# Main_Schematics.net
KiCad netlist of a schematic drawn in Altium Designer
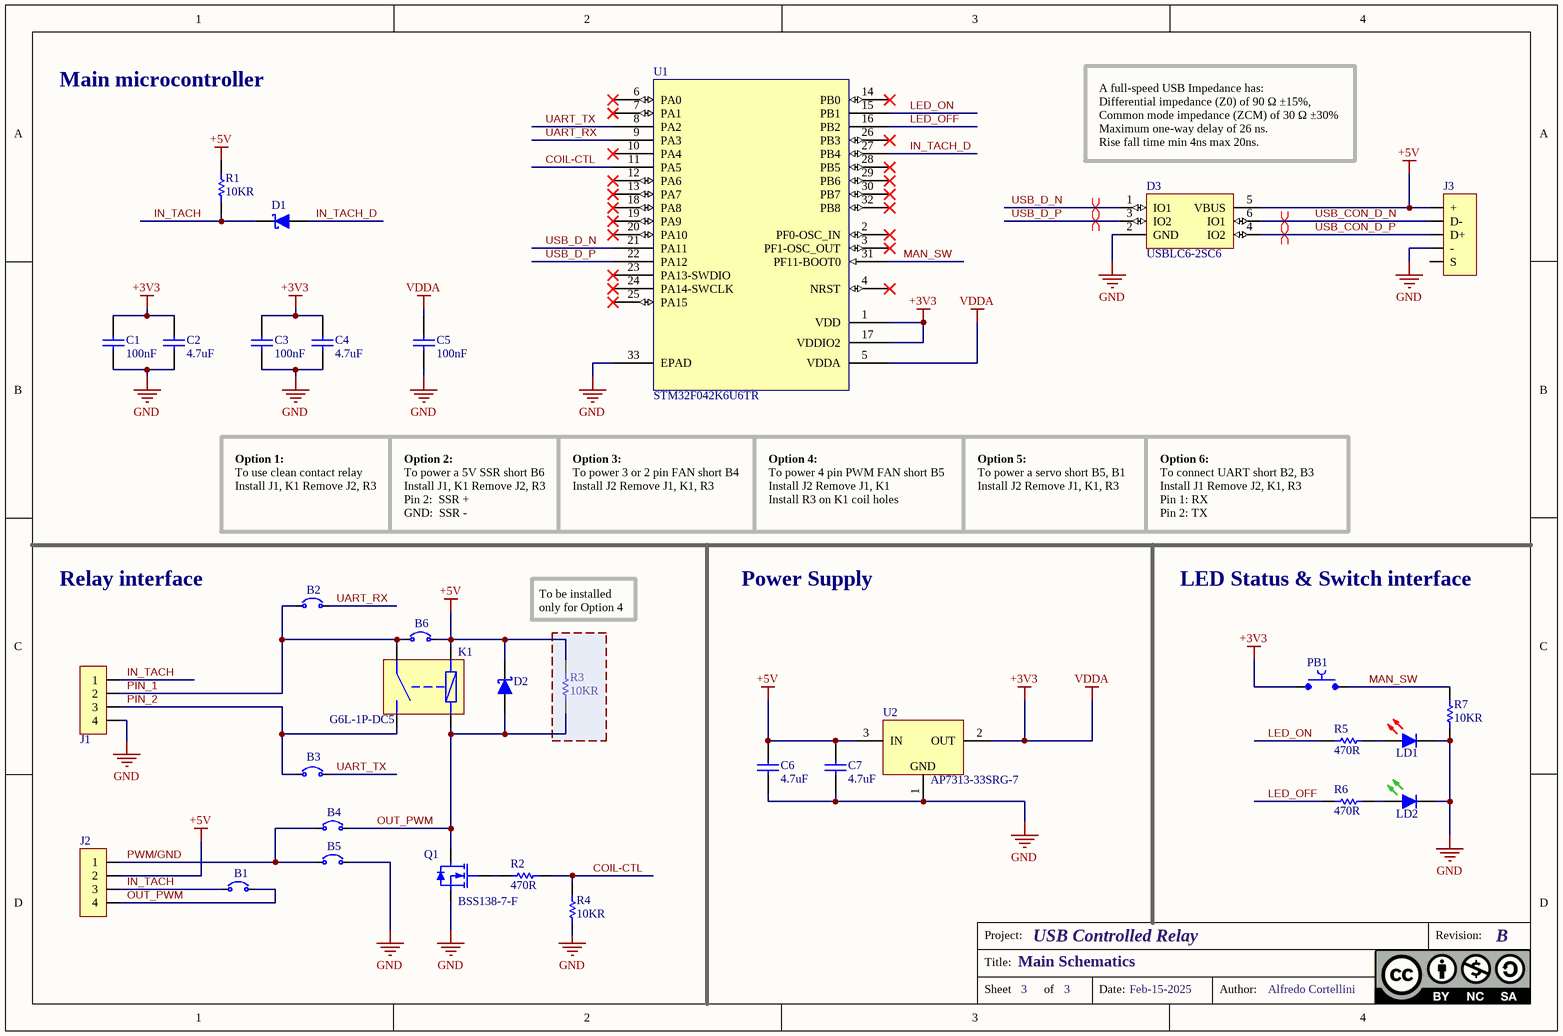
[diagram p0: Main Schematics.SchDoc]

(export (version "E")
  (design (tool "Eeschema 10.0.6"))
  (components
    (comp (ref "B1")
      (value "_SMD-JUMP-0603")
      (footprint "_SMD-JUMP-0603")
      (description "Option Jumper smd 0603")
      (libsource (lib "IT Logic Library") (part "_SMD-JUMP-0603"))
    )
    (comp (ref "B2")
      (value "_SMD-JUMP-0603")
      (footprint "_SMD-JUMP-0603")
      (description "Option Jumper smd 0603")
      (libsource (lib "IT Logic Library") (part "_SMD-JUMP-0603"))
    )
    (comp (ref "B3")
      (value "_SMD-JUMP-0603")
      (footprint "_SMD-JUMP-0603")
      (description "Option Jumper smd 0603")
      (libsource (lib "IT Logic Library") (part "_SMD-JUMP-0603"))
    )
    (comp (ref "B4")
      (value "_SMD-JUMP-0603")
      (footprint "_SMD-JUMP-0603")
      (description "Option Jumper smd 0603")
      (libsource (lib "IT Logic Library") (part "_SMD-JUMP-0603"))
    )
    (comp (ref "B5")
      (value "_SMD-JUMP-0603")
      (footprint "_SMD-JUMP-0603")
      (description "Option Jumper smd 0603")
      (libsource (lib "IT Logic Library") (part "_SMD-JUMP-0603"))
    )
    (comp (ref "B6")
      (value "_SMD-JUMP-0603")
      (footprint "_SMD-JUMP-0603")
      (description "Option Jumper smd 0603")
      (libsource (lib "IT Logic Library") (part "_SMD-JUMP-0603"))
    )
    (comp (ref "C1")
      (value "100nF")
      (footprint "C0603-H90")
      (description "Cap 0603 Case Ceramic 100nF 50V X7R")
      (fields
        (field (name "MANUFACTURER") "TDK")
        (field (name "MANUFACTURER PART NUMBER") "CGA3E2X7R1H104K080AA")
      )
      (libsource (lib "IT Logic Library") (part "CGA3E2X7R1H104K080AA"))
    )
    (comp (ref "C2")
      (value "4.7uF")
      (footprint "C0603-H90")
      (description "Cap 0603 Case Ceramic 4.7uF 16V X7R")
      (fields
        (field (name "MANUFACTURER") "Murata")
        (field (name "MANUFACTURER PART NUMBER") "GRM188Z71C475KE21D")
      )
      (libsource (lib "IT Logic Library") (part "GRM188Z71C475KE21D"))
    )
    (comp (ref "C3")
      (value "100nF")
      (footprint "C0603-H90")
      (description "Cap 0603 Case Ceramic 100nF 50V X7R")
      (fields
        (field (name "MANUFACTURER") "TDK")
        (field (name "MANUFACTURER PART NUMBER") "CGA3E2X7R1H104K080AA")
      )
      (libsource (lib "IT Logic Library") (part "CGA3E2X7R1H104K080AA"))
    )
    (comp (ref "C4")
      (value "4.7uF")
      (footprint "C0603-H90")
      (description "Cap 0603 Case Ceramic 4.7uF 16V X7R")
      (fields
        (field (name "MANUFACTURER") "Murata")
        (field (name "MANUFACTURER PART NUMBER") "GRM188Z71C475KE21D")
      )
      (libsource (lib "IT Logic Library") (part "GRM188Z71C475KE21D"))
    )
    (comp (ref "C5")
      (value "100nF")
      (footprint "C0603-H90")
      (description "Cap 0603 Case Ceramic 100nF 50V X7R")
      (fields
        (field (name "MANUFACTURER") "TDK")
        (field (name "MANUFACTURER PART NUMBER") "CGA3E2X7R1H104K080AA")
      )
      (libsource (lib "IT Logic Library") (part "CGA3E2X7R1H104K080AA"))
    )
    (comp (ref "C6")
      (value "4.7uF")
      (footprint "C0603-H90")
      (description "Cap 0603 Case Ceramic 4.7uF 16V X7R")
      (fields
        (field (name "MANUFACTURER") "Murata")
        (field (name "MANUFACTURER PART NUMBER") "GRM188Z71C475KE21D")
      )
      (libsource (lib "IT Logic Library") (part "GRM188Z71C475KE21D"))
    )
    (comp (ref "C7")
      (value "4.7uF")
      (footprint "C0603-H90")
      (description "Cap 0603 Case Ceramic 4.7uF 16V X7R")
      (fields
        (field (name "MANUFACTURER") "Murata")
        (field (name "MANUFACTURER PART NUMBER") "GRM188Z71C475KE21D")
      )
      (libsource (lib "IT Logic Library") (part "GRM188Z71C475KE21D"))
    )
    (comp (ref "D1")
      (value "BAT54WS-7-F")
      (footprint "SOD-323")
      (description "Diode Schottky 30V 0.1A, Vf 400mV@10mA SOD-323")
      (fields (field (name "MANUFACTURER") "Diodes"))
      (libsource (lib "IT Logic Library") (part "BAT54WS-7-F"))
    )
    (comp (ref "D2")
      (value "BAT54WS-7-F")
      (footprint "SOD-323")
      (description "Diode Schottky 30V 0.1A, Vf 400mV@10mA SOD-323")
      (fields (field (name "MANUFACTURER") "Diodes"))
      (libsource (lib "IT Logic Library") (part "BAT54WS-7-F"))
    )
    (comp (ref "D3")
      (value "USBLC6-2SC6")
      (footprint "SOT-236")
      (description "ESD Protection Diodes / TVS Diodes 2 Line 2.5pF USB 2.0 ESD Protect SOT23-6")
      (fields (field (name "MANUFACTURER") "STMicroelectronics"))
      (libsource (lib "IT Logic Library") (part "USBLC6-2SC6"))
    )
    (comp (ref "J1")
      (value "691210910004")
      (footprint "691210910004")
      (description "Conn Term Block Header Screw 2.54 mm 4 Pos 6A 150V")
      (fields (field (name "MANUFACTURER") "Wurth Electronics"))
      (libsource (lib "IT Logic Library") (part "691210910004"))
    )
    (comp (ref "J2")
      (value "CO975")
      (footprint "FAN-HDR-4P-90DEG")
      (description "Conn Post Header - PWM Fan - 90 Deg - 4 Pos - Series KK254")
      (fields (field (name "MANUFACTURER") "Moddy"))
      (libsource (lib "IT Logic Library") (part "CO975"))
    )
    (comp (ref "J3")
      (value "USB-AP-S-RA")
      (footprint "48037-0001")
      (description "Conn USB Type A Plug Right-Anglel TH")
      (fields (field (name "MANUFACTURER") "Adam Tech"))
      (libsource (lib "IT Logic Library") (part "USB-AP-S-RA"))
    )
    (comp (ref "K1")
      (value "G6L-1P-DC5")
      (footprint "G6L-1P")
      (description "Relay Low Signal Sealed SPST-NO 1A 5VDC Through Hole Tube")
      (fields (field (name "MANUFACTURER") "Omron"))
      (libsource (lib "IT Logic Library") (part "G6L-1P-DC5"))
    )
    (comp (ref "LD1")
      (value "LTST-C191KRKT")
      (footprint "LED-0603-R")
      (description "LED 0603 Top Red 631nm 2-Pin")
      (fields (field (name "MANUFACTURER") "Vishay Semiconductors"))
      (libsource (lib "IT Logic Library") (part "LTST-C191KRKT"))
    )
    (comp (ref "LD2")
      (value "LTST-C191KGKT")
      (footprint "LED-0603-G")
      (description "LED 0603 Top Green 571nm 2-Pin")
      (fields (field (name "MANUFACTURER") "Vishay Semiconductors"))
      (libsource (lib "IT Logic Library") (part "LTST-C191KGKT"))
    )
    (comp (ref "PB1")
      (value "SKQMAQE010")
      (footprint "SKQMA-SERIE")
      (description "Tactile Switch Rectangular 6.00x3.55mm. Height 4.3mm. J-Lead 50mA 12VDC 260gf SMD")
      (fields (field (name "MANUFACTURER") "Alps Alpine"))
      (libsource (lib "IT Logic Library") (part "SKQMAQE010"))
    )
    (comp (ref "Q1")
      (value "BSS138-7-F")
      (footprint "SOT-23")
      (description "Mosfet N 50V Vds 20V Vgs 1.4R SOT-23")
      (fields (field (name "MANUFACTURER") "Diodes"))
      (libsource (lib "IT Logic Library") (part "BSS138-7-F"))
    )
    (comp (ref "R1")
      (value "10KR")
      (footprint "R0603-H55")
      (description "Resistor 0603 Case 10KR 1% 1/10W")
      (fields
        (field (name "MANUFACTURER") "Yageo")
        (field (name "MANUFACTURER PART NUMBER") "RC0603FR-0710KL")
      )
      (libsource (lib "IT Logic Library") (part "RC0603FR-0710KL"))
    )
    (comp (ref "R2")
      (value "470R")
      (footprint "R0603-H55")
      (description "Resistor 0603 Case 470R 1% 1/10W")
      (fields
        (field (name "MANUFACTURER") "Yageo")
        (field (name "MANUFACTURER PART NUMBER") "RC0603FR-07470RL")
      )
      (libsource (lib "IT Logic Library") (part "RC0603FR-07470RL"))
    )
    (comp (ref "R3")
      (value "10KR")
      (footprint "RAXIAL-1/8W")
      (description "Resistor Axial 10KR 1% 1/8W")
      (fields
        (field (name "MANUFACTURER") "SEI Stackpole")
        (field (name "MANUFACTURER PART NUMBER") "RNF18FTD10K0")
      )
      (libsource (lib "IT Logic Library") (part "RNF18FTD10K0"))
    )
    (comp (ref "R4")
      (value "10KR")
      (footprint "R0603-H55")
      (description "Resistor 0603 Case 10KR 1% 1/10W")
      (fields
        (field (name "MANUFACTURER") "Yageo")
        (field (name "MANUFACTURER PART NUMBER") "RC0603FR-0710KL")
      )
      (libsource (lib "IT Logic Library") (part "RC0603FR-0710KL"))
    )
    (comp (ref "R5")
      (value "470R")
      (footprint "R0603-H55")
      (description "Resistor 0603 Case 470R 1% 1/10W")
      (fields
        (field (name "MANUFACTURER") "Yageo")
        (field (name "MANUFACTURER PART NUMBER") "RC0603FR-07470RL")
      )
      (libsource (lib "IT Logic Library") (part "RC0603FR-07470RL"))
    )
    (comp (ref "R6")
      (value "470R")
      (footprint "R0603-H55")
      (description "Resistor 0603 Case 470R 1% 1/10W")
      (fields
        (field (name "MANUFACTURER") "Yageo")
        (field (name "MANUFACTURER PART NUMBER") "RC0603FR-07470RL")
      )
      (libsource (lib "IT Logic Library") (part "RC0603FR-07470RL"))
    )
    (comp (ref "R7")
      (value "10KR")
      (footprint "R0603-H55")
      (description "Resistor 0603 Case 10KR 1% 1/10W")
      (fields
        (field (name "MANUFACTURER") "Yageo")
        (field (name "MANUFACTURER PART NUMBER") "RC0603FR-0710KL")
      )
      (libsource (lib "IT Logic Library") (part "RC0603FR-0710KL"))
    )
    (comp (ref "U1")
      (value "STM32F042K6U6TR")
      (footprint "UFQFPN32-5x5")
      (description "STM32 Arm Cortex-M0 USB line MCU 32 Kbytes of Flash 48 MHz CPU USB CAN CEC")
      (fields (field (name "MANUFACTURER") "STMicroelectronics"))
      (libsource (lib "IT Logic Library") (part "STM32F042K6U6TR"))
    )
    (comp (ref "U2")
      (value "AP7313-33SRG-7")
      (footprint "SOT-23")
      (description "LDO 3.3V 150mA Out  6Vin 130mV Dropout, Quiescent current 65uA Startup 80µs SOT-23")
      (fields (field (name "MANUFACTURER") "Diodes"))
      (libsource (lib "IT Logic Library") (part "AP7313-33SRG-7"))
    )
  )
  (nets
    (net (code "1") (name "+3V3") (class "Default")
      (node (ref "C1") (pin "2") (pinfunction "2_2") (pintype "passive"))
      (node (ref "C2") (pin "2") (pinfunction "2_2") (pintype "passive"))
      (node (ref "C3") (pin "2") (pinfunction "2_2") (pintype "passive"))
      (node (ref "C4") (pin "2") (pinfunction "2_2") (pintype "passive"))
      (node (ref "C5") (pin "2") (pinfunction "2_2") (pintype "passive"))
      (node (ref "PB1") (pin "1") (pinfunction "1_1") (pintype "passive"))
      (node (ref "U1") (pin "1") (pinfunction "VDD_1") (pintype "power_in"))
      (node (ref "U1") (pin "17") (pinfunction "VDDIO2_17") (pintype "power_in"))
      (node (ref "U1") (pin "5") (pinfunction "VDDA_5") (pintype "power_in"))
      (node (ref "U2") (pin "2") (pinfunction "OUT_2") (pintype "power_in"))
    )
    (net (code "2") (name "+5V") (class "Default")
      (node (ref "B6") (pin "1") (pinfunction "1_1") (pintype "passive"))
      (node (ref "C6") (pin "2") (pinfunction "2_2") (pintype "passive"))
      (node (ref "C7") (pin "2") (pinfunction "2_2") (pintype "passive"))
      (node (ref "D2") (pin "1") (pinfunction "K_1") (pintype "passive"))
      (node (ref "D3") (pin "5") (pinfunction "VBUS_5") (pintype "power_in"))
      (node (ref "J2") (pin "2") (pinfunction "2_2") (pintype "passive"))
      (node (ref "J3") (pin "1") (pinfunction "+_1") (pintype "passive"))
      (node (ref "K1") (pin "8") (pintype "passive"))
      (node (ref "R1") (pin "2") (pinfunction "2_2") (pintype "passive"))
      (node (ref "R3") (pin "2") (pinfunction "2_2") (pintype "passive"))
      (node (ref "U2") (pin "3") (pinfunction "IN_3") (pintype "power_in"))
    )
    (net (code "3") (name "/COIL-CTL") (class "Default")
      (node (ref "R2") (pin "2") (pinfunction "2_2") (pintype "passive"))
      (node (ref "R4") (pin "2") (pinfunction "2_2") (pintype "passive"))
      (node (ref "U1") (pin "11") (pinfunction "PA5_11") (pintype "passive"))
    )
    (net (code "4") (name "/IN_TACH") (class "Default")
      (node (ref "B1") (pin "2") (pinfunction "2_2") (pintype "passive"))
      (node (ref "D1") (pin "1") (pinfunction "K_1") (pintype "passive"))
      (node (ref "J1") (pin "1") (pinfunction "1_1") (pintype "passive"))
      (node (ref "J2") (pin "3") (pinfunction "3_3") (pintype "passive"))
      (node (ref "R1") (pin "1") (pinfunction "1_1") (pintype "passive"))
    )
    (net (code "5") (name "/IN_TACH_D") (class "Default")
      (node (ref "D1") (pin "2") (pinfunction "A_2") (pintype "passive"))
      (node (ref "U1") (pin "27") (pinfunction "PB4_27") (pintype "bidirectional"))
    )
    (net (code "6") (name "/LED_OFF") (class "Default")
      (node (ref "R6") (pin "1") (pinfunction "1_1") (pintype "passive"))
      (node (ref "U1") (pin "16") (pinfunction "PB2_16") (pintype "passive"))
    )
    (net (code "7") (name "/LED_ON") (class "Default")
      (node (ref "R5") (pin "1") (pinfunction "1_1") (pintype "passive"))
      (node (ref "U1") (pin "15") (pinfunction "PB1_15") (pintype "passive"))
    )
    (net (code "8") (name "/MAN_SW") (class "Default")
      (node (ref "PB1") (pin "2") (pinfunction "2_2") (pintype "passive"))
      (node (ref "R7") (pin "2") (pinfunction "2_2") (pintype "passive"))
      (node (ref "U1") (pin "31") (pinfunction "PF11-BOOT0_31") (pintype "input"))
    )
    (net (code "9") (name "/OUT_PWM") (class "Default")
      (node (ref "B1") (pin "1") (pinfunction "1_1") (pintype "passive"))
      (node (ref "B4") (pin "1") (pinfunction "1_1") (pintype "passive"))
      (node (ref "D2") (pin "2") (pinfunction "A_2") (pintype "passive"))
      (node (ref "J2") (pin "4") (pinfunction "4_4") (pintype "passive"))
      (node (ref "K1") (pin "5") (pintype "passive"))
      (node (ref "Q1") (pin "3") (pinfunction "D_3") (pintype "passive"))
      (node (ref "R3") (pin "1") (pinfunction "1_1") (pintype "passive"))
    )
    (net (code "10") (name "/PIN_1") (class "Default")
      (node (ref "B2") (pin "2") (pinfunction "2_2") (pintype "passive"))
      (node (ref "B6") (pin "2") (pinfunction "2_2") (pintype "passive"))
      (node (ref "J1") (pin "2") (pinfunction "2_2") (pintype "passive"))
      (node (ref "K1") (pin "2") (pinfunction "C_2") (pintype "passive"))
    )
    (net (code "11") (name "/PIN_2") (class "Default")
      (node (ref "B3") (pin "2") (pinfunction "2_2") (pintype "passive"))
      (node (ref "J1") (pin "3") (pinfunction "3_3") (pintype "passive"))
      (node (ref "K1") (pin "4") (pinfunction "NO_4") (pintype "passive"))
    )
    (net (code "12") (name "/PWM{slash}GND") (class "Default")
      (node (ref "B4") (pin "2") (pinfunction "2_2") (pintype "passive"))
      (node (ref "B5") (pin "2") (pinfunction "2_2") (pintype "passive"))
      (node (ref "J2") (pin "1") (pinfunction "1_1") (pintype "passive"))
    )
    (net (code "13") (name "/UART_RX") (class "Default")
      (node (ref "B2") (pin "1") (pinfunction "1_1") (pintype "passive"))
      (node (ref "U1") (pin "9") (pinfunction "PA3_9") (pintype "passive"))
    )
    (net (code "14") (name "/UART_TX") (class "Default")
      (node (ref "B3") (pin "1") (pinfunction "1_1") (pintype "passive"))
      (node (ref "U1") (pin "8") (pinfunction "PA2_8") (pintype "passive"))
    )
    (net (code "15") (name "/USB_CON_D_N") (class "Default")
      (node (ref "D3") (pin "6") (pinfunction "IO1_6") (pintype "bidirectional"))
      (node (ref "J3") (pin "2") (pinfunction "D-_2") (pintype "passive"))
    )
    (net (code "16") (name "/USB_CON_D_P") (class "Default")
      (node (ref "D3") (pin "4") (pinfunction "IO2_4") (pintype "bidirectional"))
      (node (ref "J3") (pin "3") (pinfunction "D+_3") (pintype "passive"))
    )
    (net (code "17") (name "/USB_D_N") (class "Default")
      (node (ref "D3") (pin "1") (pinfunction "IO1_1") (pintype "bidirectional"))
      (node (ref "U1") (pin "21") (pinfunction "PA11_21") (pintype "passive"))
    )
    (net (code "18") (name "/USB_D_P") (class "Default")
      (node (ref "D3") (pin "3") (pinfunction "IO2_3") (pintype "bidirectional"))
      (node (ref "U1") (pin "22") (pinfunction "PA12_22") (pintype "passive"))
    )
    (net (code "19") (name "GND") (class "Default")
      (node (ref "B5") (pin "1") (pinfunction "1_1") (pintype "passive"))
      (node (ref "C1") (pin "1") (pinfunction "1_1") (pintype "passive"))
      (node (ref "C2") (pin "1") (pinfunction "1_1") (pintype "passive"))
      (node (ref "C3") (pin "1") (pinfunction "1_1") (pintype "passive"))
      (node (ref "C4") (pin "1") (pinfunction "1_1") (pintype "passive"))
      (node (ref "C5") (pin "1") (pinfunction "1_1") (pintype "passive"))
      (node (ref "C6") (pin "1") (pinfunction "1_1") (pintype "passive"))
      (node (ref "C7") (pin "1") (pinfunction "1_1") (pintype "passive"))
      (node (ref "D3") (pin "2") (pinfunction "GND_2") (pintype "power_in"))
      (node (ref "J1") (pin "4") (pinfunction "4_4") (pintype "passive"))
      (node (ref "J3") (pin "4") (pinfunction "-_4") (pintype "passive"))
      (node (ref "LD1") (pin "1") (pinfunction "K_1") (pintype "passive"))
      (node (ref "LD2") (pin "1") (pinfunction "K_1") (pintype "passive"))
      (node (ref "Q1") (pin "2") (pinfunction "S_2") (pintype "passive"))
      (node (ref "R4") (pin "1") (pinfunction "1_1") (pintype "passive"))
      (node (ref "R7") (pin "1") (pinfunction "1_1") (pintype "passive"))
      (node (ref "U1") (pin "33") (pinfunction "EPAD_33") (pintype "passive"))
      (node (ref "U2") (pin "1") (pinfunction "GND_1") (pintype "power_in"))
    )
    (net (code "20") (name "Net-(LD1-A)") (class "Default")
      (node (ref "LD1") (pin "2") (pinfunction "A_2") (pintype "passive"))
      (node (ref "R5") (pin "2") (pinfunction "2_2") (pintype "passive"))
    )
    (net (code "21") (name "Net-(LD2-A)") (class "Default")
      (node (ref "LD2") (pin "2") (pinfunction "A_2") (pintype "passive"))
      (node (ref "R6") (pin "2") (pinfunction "2_2") (pintype "passive"))
    )
    (net (code "22") (name "Net-(Q1-G)") (class "Default")
      (node (ref "Q1") (pin "1") (pinfunction "G_1") (pintype "passive"))
      (node (ref "R2") (pin "1") (pinfunction "1_1") (pintype "passive"))
    )
    (net (code "23") (name "unconnected-(J3-PadS)") (class "Default")
      (node (ref "J3") (pin "S") (pinfunction "S_S") (pintype "passive"))
    )
    (net (code "24") (name "unconnected-(U1-NRST-Pad4)") (class "Default")
      (node (ref "U1") (pin "4") (pinfunction "NRST_4") (pintype "bidirectional+no_connect"))
    )
    (net (code "25") (name "unconnected-(U1-PA0-Pad6)") (class "Default")
      (node (ref "U1") (pin "6") (pinfunction "PA0_6") (pintype "bidirectional+no_connect"))
    )
    (net (code "26") (name "unconnected-(U1-PA1-Pad7)") (class "Default")
      (node (ref "U1") (pin "7") (pinfunction "PA1_7") (pintype "bidirectional+no_connect"))
    )
    (net (code "27") (name "unconnected-(U1-PA4-Pad10)") (class "Default")
      (node (ref "U1") (pin "10") (pinfunction "PA4_10") (pintype "passive+no_connect"))
    )
    (net (code "28") (name "unconnected-(U1-PA6-Pad12)") (class "Default")
      (node (ref "U1") (pin "12") (pinfunction "PA6_12") (pintype "bidirectional+no_connect"))
    )
    (net (code "29") (name "unconnected-(U1-PA7-Pad13)") (class "Default")
      (node (ref "U1") (pin "13") (pinfunction "PA7_13") (pintype "bidirectional+no_connect"))
    )
    (net (code "30") (name "unconnected-(U1-PA8-Pad18)") (class "Default")
      (node (ref "U1") (pin "18") (pinfunction "PA8_18") (pintype "bidirectional+no_connect"))
    )
    (net (code "31") (name "unconnected-(U1-PA9-Pad19)") (class "Default")
      (node (ref "U1") (pin "19") (pinfunction "PA9_19") (pintype "bidirectional+no_connect"))
    )
    (net (code "32") (name "unconnected-(U1-PA10-Pad20)") (class "Default")
      (node (ref "U1") (pin "20") (pinfunction "PA10_20") (pintype "bidirectional+no_connect"))
    )
    (net (code "33") (name "unconnected-(U1-PA13-SWDIO-Pad23)") (class "Default")
      (node (ref "U1") (pin "23") (pinfunction "PA13-SWDIO_23") (pintype "passive+no_connect"))
    )
    (net (code "34") (name "unconnected-(U1-PA14-SWCLK-Pad24)") (class "Default")
      (node (ref "U1") (pin "24") (pinfunction "PA14-SWCLK_24") (pintype "passive+no_connect"))
    )
    (net (code "35") (name "unconnected-(U1-PA15-Pad25)") (class "Default")
      (node (ref "U1") (pin "25") (pinfunction "PA15_25") (pintype "bidirectional+no_connect"))
    )
    (net (code "36") (name "unconnected-(U1-PB0-Pad14)") (class "Default")
      (node (ref "U1") (pin "14") (pinfunction "PB0_14") (pintype "bidirectional+no_connect"))
    )
    (net (code "37") (name "unconnected-(U1-PB3-Pad26)") (class "Default")
      (node (ref "U1") (pin "26") (pinfunction "PB3_26") (pintype "bidirectional+no_connect"))
    )
    (net (code "38") (name "unconnected-(U1-PB5-Pad28)") (class "Default")
      (node (ref "U1") (pin "28") (pinfunction "PB5_28") (pintype "bidirectional+no_connect"))
    )
    (net (code "39") (name "unconnected-(U1-PB6-Pad29)") (class "Default")
      (node (ref "U1") (pin "29") (pinfunction "PB6_29") (pintype "bidirectional+no_connect"))
    )
    (net (code "40") (name "unconnected-(U1-PB7-Pad30)") (class "Default")
      (node (ref "U1") (pin "30") (pinfunction "PB7_30") (pintype "bidirectional+no_connect"))
    )
    (net (code "41") (name "unconnected-(U1-PB8-Pad32)") (class "Default")
      (node (ref "U1") (pin "32") (pinfunction "PB8_32") (pintype "bidirectional+no_connect"))
    )
    (net (code "42") (name "unconnected-(U1-PF0-OSC_IN-Pad2)") (class "Default")
      (node (ref "U1") (pin "2") (pinfunction "PF0-OSC_IN_2") (pintype "bidirectional+no_connect"))
    )
    (net (code "43") (name "unconnected-(U1-PF1-OSC_OUT-Pad3)") (class "Default")
      (node (ref "U1") (pin "3") (pinfunction "PF1-OSC_OUT_3") (pintype "bidirectional+no_connect"))
    )
  )
)
